# GPIO_EXPANDER_A.net
KiCad netlist of a schematic drawn in Altium Designer
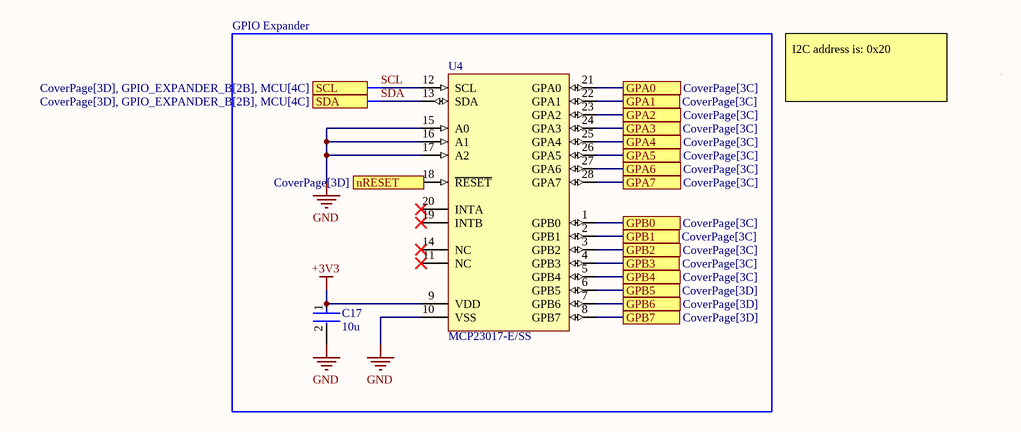
[diagram p0: GPIO_EXPANDER_A.SchDoc]

(export (version "E")
  (design (tool "Eeschema 10.0.6"))
  (components
    (comp (ref "C17")
      (value "10u")
      (footprint "FP-C0805C-DG-MFG")
      (description "CAP CER 10UF 10V X5R 0805")
      (fields (field (name "TOLERANCE") "10%") (field (name "MANUFACTURER PART NUMBER") "C0805C106K8PACTU"))
      (libsource (lib "Altium Content Vault") (part "11868f565c42a9108669ba33697ecf6"))
    )
    (comp (ref "U4")
      (value "MCP23017-E/SS")
      (footprint "SSOP-SS28_N")
      (description "16-Bit I/O Expander with Serial Interface, 28-Pin SSOP, Extended Temperature")
      (libsource (lib "Altium Content Vault") (part "PR-BUSIC-MCP23017-28"))
    )
  )
  (nets
    (net (code "1") (name "+3V3") (class "Default")
      (node (ref "C17") (pin "1") (pinfunction "1_1") (pintype "passive"))
      (node (ref "U4") (pin "9") (pinfunction "VDD_9") (pintype "power_in"))
    )
    (net (code "2") (name "/GPA0") (class "Default")
      (node (ref "U4") (pin "21") (pinfunction "GPA0_21") (pintype "bidirectional"))
    )
    (net (code "3") (name "/GPA1") (class "Default")
      (node (ref "U4") (pin "22") (pinfunction "GPA1_22") (pintype "bidirectional"))
    )
    (net (code "4") (name "/GPA2") (class "Default")
      (node (ref "U4") (pin "23") (pinfunction "GPA2_23") (pintype "bidirectional"))
    )
    (net (code "5") (name "/GPA3") (class "Default")
      (node (ref "U4") (pin "24") (pinfunction "GPA3_24") (pintype "bidirectional"))
    )
    (net (code "6") (name "/GPA4") (class "Default")
      (node (ref "U4") (pin "25") (pinfunction "GPA4_25") (pintype "bidirectional"))
    )
    (net (code "7") (name "/GPA5") (class "Default")
      (node (ref "U4") (pin "26") (pinfunction "GPA5_26") (pintype "bidirectional"))
    )
    (net (code "8") (name "/GPA6") (class "Default")
      (node (ref "U4") (pin "27") (pinfunction "GPA6_27") (pintype "bidirectional"))
    )
    (net (code "9") (name "/GPA7") (class "Default")
      (node (ref "U4") (pin "28") (pinfunction "GPA7_28") (pintype "bidirectional"))
    )
    (net (code "10") (name "/GPB0") (class "Default")
      (node (ref "U4") (pin "1") (pinfunction "GPB0_1") (pintype "bidirectional"))
    )
    (net (code "11") (name "/GPB1") (class "Default")
      (node (ref "U4") (pin "2") (pinfunction "GPB1_2") (pintype "bidirectional"))
    )
    (net (code "12") (name "/GPB2") (class "Default")
      (node (ref "U4") (pin "3") (pinfunction "GPB2_3") (pintype "bidirectional"))
    )
    (net (code "13") (name "/GPB3") (class "Default")
      (node (ref "U4") (pin "4") (pinfunction "GPB3_4") (pintype "bidirectional"))
    )
    (net (code "14") (name "/GPB4") (class "Default")
      (node (ref "U4") (pin "5") (pinfunction "GPB4_5") (pintype "bidirectional"))
    )
    (net (code "15") (name "/GPB5") (class "Default")
      (node (ref "U4") (pin "6") (pinfunction "GPB5_6") (pintype "bidirectional"))
    )
    (net (code "16") (name "/GPB6") (class "Default")
      (node (ref "U4") (pin "7") (pinfunction "GPB6_7") (pintype "bidirectional"))
    )
    (net (code "17") (name "/GPB7") (class "Default")
      (node (ref "U4") (pin "8") (pinfunction "GPB7_8") (pintype "bidirectional"))
    )
    (net (code "18") (name "/SCL") (class "Default")
      (node (ref "U4") (pin "12") (pinfunction "SCL_12") (pintype "input"))
    )
    (net (code "19") (name "/SDA") (class "Default")
      (node (ref "U4") (pin "13") (pinfunction "SDA_13") (pintype "bidirectional"))
    )
    (net (code "21") (name "GND") (class "Default")
      (node (ref "C17") (pin "2") (pinfunction "2_2") (pintype "passive"))
      (node (ref "U4") (pin "10") (pinfunction "VSS_10") (pintype "power_in"))
      (node (ref "U4") (pin "15") (pinfunction "A0_15") (pintype "input"))
      (node (ref "U4") (pin "16") (pinfunction "A1_16") (pintype "input"))
      (node (ref "U4") (pin "17") (pinfunction "A2_17") (pintype "input"))
    )
    (net (code "22") (name "unconnected-(U4-INTA-Pad20)") (class "Default")
      (node (ref "U4") (pin "20") (pinfunction "INTA_20") (pintype "open_collector+no_connect"))
    )
    (net (code "23") (name "unconnected-(U4-INTB-Pad19)") (class "Default")
      (node (ref "U4") (pin "19") (pinfunction "INTB_19") (pintype "open_collector+no_connect"))
    )
    (net (code "24") (name "unconnected-(U4-NC-Pad11)") (class "Default")
      (node (ref "U4") (pin "11") (pinfunction "NC_11") (pintype "passive+no_connect"))
    )
    (net (code "25") (name "unconnected-(U4-NC-Pad14)") (class "Default")
      (node (ref "U4") (pin "14") (pinfunction "NC_14") (pintype "passive+no_connect"))
    )
    (net (code "26") (name "unconnected-(U4-~{RESET}-Pad18)") (class "Default")
      (node (ref "U4") (pin "18") (pinfunction "~{RESET}_18") (pintype "input"))
    )
  )
)
